# DAP-Link.net
KiCad netlist of a schematic drawn in Altium Designer
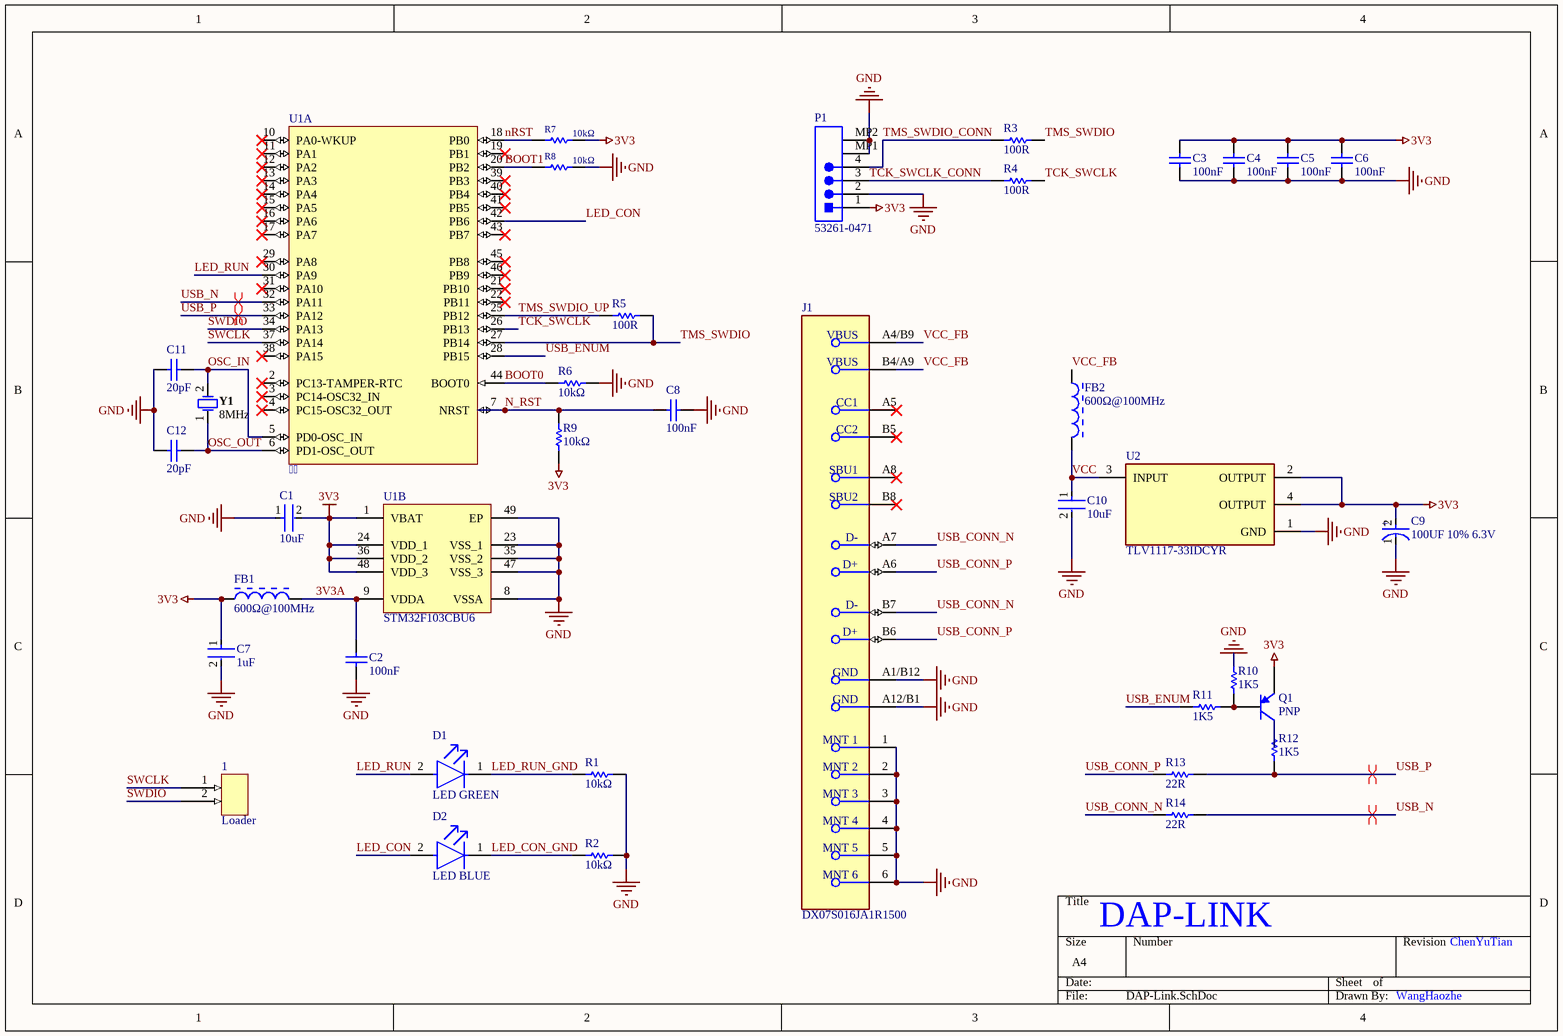
[diagram p0: DAP-Link.SchDoc]

(export (version "E")
  (design (tool "Eeschema 10.0.6"))
  (components
    (comp (ref "1") (value "Loader") (footprint "Loader") (libsource (lib "Loader") (part "Loader")))
    (comp (ref "C1")
      (value "10uF")
      (footprint "FP-CL10-IPC_C")
      (description "Cap Ceramic 10uF 25V X5R ±20% Pad SMD 0603 +85°C T/R")
      (fields (field (name "TOLERANCE") "20%"))
      (libsource (lib "Altium Content Vault") (part "b4654b650e69147ec39a6b967a45e02"))
    )
    (comp (ref "C2")
      (value "100nF")
      (footprint "CAPC1050X55X23ML05T13")
      (description "Chip Capacitor, 100 nF, +/- 10%, 16 V, -55 to 125 degC, 0402 (1005 Metric), RoHS, Tape and Reel")
      (fields (field (name "MANUFACTURER") "Samsung Electro-Mechanics"))
      (libsource (lib "Altium Content Vault") (part "CAP-NP-2"))
    )
    (comp (ref "C3")
      (value "100nF")
      (footprint "CAPC1050X55X23ML05T13")
      (description "Chip Capacitor, 100 nF, +/- 10%, 16 V, -55 to 125 degC, 0402 (1005 Metric), RoHS, Tape and Reel")
      (fields (field (name "MANUFACTURER") "Samsung Electro-Mechanics"))
      (libsource (lib "Altium Content Vault") (part "CAP-NP-2"))
    )
    (comp (ref "C4")
      (value "100nF")
      (footprint "CAPC1050X55X23ML05T13")
      (description "Chip Capacitor, 100 nF, +/- 10%, 16 V, -55 to 125 degC, 0402 (1005 Metric), RoHS, Tape and Reel")
      (fields (field (name "MANUFACTURER") "Samsung Electro-Mechanics"))
      (libsource (lib "Altium Content Vault") (part "CAP-NP-2"))
    )
    (comp (ref "C5")
      (value "100nF")
      (footprint "CAPC1050X55X23ML05T13")
      (description "Chip Capacitor, 100 nF, +/- 10%, 16 V, -55 to 125 degC, 0402 (1005 Metric), RoHS, Tape and Reel")
      (fields (field (name "MANUFACTURER") "Samsung Electro-Mechanics"))
      (libsource (lib "Altium Content Vault") (part "CAP-NP-2"))
    )
    (comp (ref "C6")
      (value "100nF")
      (footprint "CAPC1050X55X23ML05T13")
      (description "Chip Capacitor, 100 nF, +/- 10%, 16 V, -55 to 125 degC, 0402 (1005 Metric), RoHS, Tape and Reel")
      (fields (field (name "MANUFACTURER") "Samsung Electro-Mechanics"))
      (libsource (lib "Altium Content Vault") (part "CAP-NP-2"))
    )
    (comp (ref "C7")
      (value "1uF")
      (footprint "FP-CL542-IPC_C")
      (description "Cap Ceramic 1uF 25V X5R ±10% SMD 0402 +85°C Paper T/R")
      (fields (field (name "TOLERANCE") "10%"))
      (libsource (lib "Altium Content Vault") (part "b4654b650e69147ec39a6b967a45e02"))
    )
    (comp (ref "C8")
      (value "100nF")
      (footprint "CAPC1050X55X23ML05T13")
      (description "Chip Capacitor, 100 nF, +/- 10%, 16 V, -55 to 125 degC, 0402 (1005 Metric), RoHS, Tape and Reel")
      (fields (field (name "MANUFACTURER") "Samsung Electro-Mechanics"))
      (libsource (lib "Altium Content Vault") (part "CAP-NP-2"))
    )
    (comp (ref "C9")
      (value "100UF 10% 6.3V")
      (footprint "FP-TAJB-MFG")
      (description "100uF 6.3V  ±10% 1.7Ω 1210  SMD Tantalum Capacitor")
      (fields (field (name "TOLERANCE") "10%") (field (name "VOLTAGE") "6.3V"))
      (libsource (lib "Altium Content Vault") (part "203bc49f2ac43e59fd269a8c329ed05"))
    )
    (comp (ref "C10")
      (value "10uF")
      (footprint "FP-CL10-IPC_C")
      (description "Cap Ceramic 10uF 25V X5R ±20% Pad SMD 0603 +85°C T/R")
      (fields (field (name "TOLERANCE") "20%"))
      (libsource (lib "Altium Content Vault") (part "b4654b650e69147ec39a6b967a45e02"))
    )
    (comp (ref "C11")
      (value "20pF")
      (footprint "CAPC1608X90X30LL10T20")
      (description "Chip Capacitor, 20 pF, +/- 5%, 50 V, -55 to 85 degC, 0603 (1608 Metric), RoHS, Tape and Reel")
      (fields (field (name "MANUFACTURER") "Samsung Electro-Mechanics"))
      (libsource (lib "Altium Content Vault") (part "CAP-NP-2"))
    )
    (comp (ref "C12")
      (value "20pF")
      (footprint "CAPC1608X90X30LL10T20")
      (description "Chip Capacitor, 20 pF, +/- 5%, 50 V, -55 to 85 degC, 0603 (1608 Metric), RoHS, Tape and Reel")
      (fields (field (name "MANUFACTURER") "Samsung Electro-Mechanics"))
      (libsource (lib "Altium Content Vault") (part "CAP-NP-2"))
    )
    (comp (ref "D1")
      (value "LED GREEN")
      (footprint "FP-LTST-C190GKT-MFG")
      (description "LED GREEN CLEAR CHIP SMD")
      (fields (field (name "VOLTAGE") "2V"))
      (libsource (lib "Altium Content Vault") (part "8706943c75ba83719d021d2fdc84c58"))
    )
    (comp (ref "D2")
      (value "LED BLUE")
      (footprint "FP-LTST-C191TBKT-MFG")
      (description "LED BLUE CLEAR CHIP SMD")
      (libsource (lib "Altium Content Vault") (part "8706943c75ba83719d021d2fdc84c58"))
    )
    (comp (ref "FB1")
      (value "600Ω@100MHz")
      (footprint "MURA-BLM18-F-H1-CHIP-2_V")
      (fields (field (name "MANUFACTURER") "Murata") (field (name "PARTNUMBER") "BLM18AG601SN1D"))
      (libsource (lib "Altium Content Vault") (part "MURA-FB-2"))
    )
    (comp (ref "FB2")
      (value "600Ω@100MHz")
      (footprint "MURA-BLM18-F-H1-CHIP-2_V")
      (fields (field (name "MANUFACTURER") "Murata") (field (name "PARTNUMBER") "BLM18AG601SN1D"))
      (libsource (lib "Altium Content Vault") (part "MURA-FB-2"))
    )
    (comp (ref "J1")
      (value "DX07S016JA1R1500")
      (footprint "FP-DX07S016JA1R1500-MFG")
      (description "CONN RCP USB2.0 TYP C 24P SMD RA")
      (libsource (lib "Altium Content Vault") (part "7f3e9989102a0f22bff9cb010881d34"))
    )
    (comp (ref "P1")
      (value "53261-0471")
      (footprint "MOLEX-53261-0471_V")
      (description "Male Header, Pitch 1.25 mm, 1 x 4 Position, Height 3.4 mm, -40 to 85 degC, RoHS, Tape and Reel")
      (fields (field (name "MANUFACTURER") "Molex"))
      (libsource (lib "Altium Content Vault") (part "CN-1P-2M-R4_A"))
    )
    (comp (ref "Q1")
      (value "PNP")
      (footprint "INF-SOT23_N")
      (description "PNP Silicon Switching Transistor, 40 V VCEO, 200 mA IC, SOT23, Reel, Green")
      (fields (field (name "MANUFACTURER") "Infineon") (field (name "PARTNUMBER") "SMBT3906"))
      (libsource (lib "Altium Content Vault") (part "INF-BJTPNP-BEC-3"))
    )
    (comp (ref "R1")
      (value "10kΩ")
      (footprint "RESC1005X40X25NL05T05")
      (fields (field (name "MANUFACTURER") "Vishay Dale") (field (name "PART NUMBER") "CRCW040210K0FKED"))
      (libsource (lib "Altium Content Vault") (part "RES"))
    )
    (comp (ref "R2")
      (value "10kΩ")
      (footprint "RESC1005X40X25NL05T05")
      (fields (field (name "MANUFACTURER") "Vishay Dale") (field (name "PART NUMBER") "CRCW040210K0FKED"))
      (libsource (lib "Altium Content Vault") (part "RES"))
    )
    (comp (ref "R3")
      (value "100R")
      (footprint "RESC1608X55X25ML10T15")
      (description "Chip Resistor, 100 Ohm, +/- 1%, 0.1 W, -55 to 155 degC, 0603 (1608 Metric), RoHS, Tape and Reel")
      (fields (field (name "TOLERANCE") "1%") (field (name "MANUFACTURER") "Yageo"))
      (libsource (lib "Altium Content Vault") (part "RES-2"))
    )
    (comp (ref "R4")
      (value "100R")
      (footprint "RESC1608X55X25ML10T15")
      (description "Chip Resistor, 100 Ohm, +/- 1%, 0.1 W, -55 to 155 degC, 0603 (1608 Metric), RoHS, Tape and Reel")
      (fields (field (name "TOLERANCE") "1%") (field (name "MANUFACTURER") "Yageo"))
      (libsource (lib "Altium Content Vault") (part "RES-2"))
    )
    (comp (ref "R5")
      (value "100R")
      (footprint "RESC1608X55X25ML10T15")
      (description "Chip Resistor, 100 Ohm, +/- 1%, 0.1 W, -55 to 155 degC, 0603 (1608 Metric), RoHS, Tape and Reel")
      (fields (field (name "TOLERANCE") "1%") (field (name "MANUFACTURER") "Yageo"))
      (libsource (lib "Altium Content Vault") (part "RES-2"))
    )
    (comp (ref "R6")
      (value "10kΩ")
      (footprint "RESC1005X40X25NL05T05")
      (fields (field (name "MANUFACTURER") "Vishay Dale") (field (name "PART NUMBER") "CRCW040210K0FKED"))
      (libsource (lib "Altium Content Vault") (part "RES"))
    )
    (comp (ref "R7")
      (value "10kΩ")
      (footprint "RESC1005X40X25NL05T05")
      (fields (field (name "MANUFACTURER") "Vishay Dale") (field (name "PART NUMBER") "CRCW040210K0FKED"))
      (libsource (lib "Altium Content Vault") (part "RES"))
    )
    (comp (ref "R8")
      (value "10kΩ")
      (footprint "RESC1005X40X25NL05T05")
      (fields (field (name "MANUFACTURER") "Vishay Dale") (field (name "PART NUMBER") "CRCW040210K0FKED"))
      (libsource (lib "Altium Content Vault") (part "RES"))
    )
    (comp (ref "R9")
      (value "10kΩ")
      (footprint "RESC1005X40X25NL05T05")
      (fields (field (name "MANUFACTURER") "Vishay Dale") (field (name "PART NUMBER") "CRCW040210K0FKED"))
      (libsource (lib "Altium Content Vault") (part "RES"))
    )
    (comp (ref "R10")
      (value "1K5")
      (footprint "RESC1005X40X25ML05T10")
      (fields (field (name "MANUFACTURER") "Yageo / Phycomp") (field (name "PART NUMBER") "RC0402FR-071K5L"))
      (libsource (lib "Altium Content Vault") (part "RES"))
    )
    (comp (ref "R11")
      (value "1K5")
      (footprint "RESC1005X40X25ML05T10")
      (fields (field (name "MANUFACTURER") "Yageo / Phycomp") (field (name "PART NUMBER") "RC0402FR-071K5L"))
      (libsource (lib "Altium Content Vault") (part "RES"))
    )
    (comp (ref "R12")
      (value "1K5")
      (footprint "RESC1005X40X25ML05T10")
      (fields (field (name "MANUFACTURER") "Yageo / Phycomp") (field (name "PART NUMBER") "RC0402FR-071K5L"))
      (libsource (lib "Altium Content Vault") (part "RES"))
    )
    (comp (ref "R13")
      (value "22R")
      (footprint "RESC1005X40X25LL05T10")
      (fields (field (name "MANUFACTURER") "Yageo / Phycomp") (field (name "PART NUMBER") "RC0402FR-0722RL"))
      (libsource (lib "Altium Content Vault") (part "RES"))
    )
    (comp (ref "R14")
      (value "22R")
      (footprint "RESC1005X40X25LL05T10")
      (fields (field (name "MANUFACTURER") "Yageo / Phycomp") (field (name "PART NUMBER") "RC0402FR-0722RL"))
      (libsource (lib "Altium Content Vault") (part "RES"))
    )
    (comp (ref "U1")
      (value "")
      (footprint "STM-UFQFPN48_N")
      (fields (field (name "PARTNUMBER") "STM32F103CBU6"))
      (libsource (lib "Altium Content Vault") (part "MC-ARM-STM32F103X8_B-SQ49"))
    )
    (comp (ref "U2")
      (value "TLV1117-33IDCYR")
      (footprint "FP-DCY0004A-MFG")
      (description "IC REG LIN 3.3V 800MA SOT223-4")
      (fields
        (field (name "MANUFACTURER") "Texas Instruments")
        (field (name "OCTOPART") "https://octopart.com/tlv1117-33idcyr-texas+instruments-669250")
      )
      (libsource (lib "Altium Content Vault") (part "d420fb9686013fb832e66295cdf4acf"))
    )
    (comp (ref "Y1")
      (value "8MHz")
      (footprint "NDK-NX3225GD-8MHZ-STD-CRA-3_V")
      (description "Crystal Unit, 8 MHz, 8 pF, -40 to 150 degC, 2-Pin SMD, RoHS, Tape and Reel")
      (fields (field (name "MANUFACTURER") "NDK"))
      (libsource (lib "Altium Content Vault") (part "XTAL-1-2-2"))
    )
  )
  (nets
    (net (code "1") (name "/3V3A") (class "Default")
      (node (ref "C2") (pin "2") (pinfunction "2_2") (pintype "passive"))
      (node (ref "FB1") (pin "2") (pinfunction "2_2") (pintype "passive"))
      (node (ref "U1") (pin "9") (pinfunction "VDDA_9") (pintype "power_in"))
    )
    (net (code "2") (name "/BOOT0") (class "Default")
      (node (ref "R6") (pin "1") (pinfunction "1_1") (pintype "passive"))
      (node (ref "U1") (pin "44") (pinfunction "BOOT0_44") (pintype "input"))
    )
    (net (code "3") (name "/BOOT1") (class "Default")
      (node (ref "R8") (pin "1") (pinfunction "1_1") (pintype "passive"))
      (node (ref "U1") (pin "20") (pinfunction "PB2_20") (pintype "bidirectional"))
    )
    (net (code "4") (name "/LED_CON") (class "Default")
      (node (ref "D2") (pin "2") (pinfunction "A_2") (pintype "passive"))
      (node (ref "U1") (pin "42") (pinfunction "PB6_42") (pintype "bidirectional"))
    )
    (net (code "5") (name "/LED_CON_GND") (class "Default")
      (node (ref "D2") (pin "1") (pinfunction "C_1") (pintype "passive"))
      (node (ref "R2") (pin "1") (pinfunction "1_1") (pintype "passive"))
    )
    (net (code "6") (name "/LED_RUN") (class "Default")
      (node (ref "D1") (pin "2") (pinfunction "A_2") (pintype "passive"))
      (node (ref "U1") (pin "30") (pinfunction "PA9_30") (pintype "bidirectional"))
    )
    (net (code "7") (name "/LED_RUN_GND") (class "Default")
      (node (ref "D1") (pin "1") (pinfunction "C_1") (pintype "passive"))
      (node (ref "R1") (pin "1") (pinfunction "1_1") (pintype "passive"))
    )
    (net (code "8") (name "/N_RST") (class "Default")
      (node (ref "C8") (pin "1") (pinfunction "1_1") (pintype "passive"))
      (node (ref "R9") (pin "1") (pinfunction "1_1") (pintype "passive"))
      (node (ref "U1") (pin "7") (pinfunction "NRST_7") (pintype "bidirectional"))
    )
    (net (code "9") (name "/OSC_IN") (class "Default")
      (node (ref "C11") (pin "2") (pinfunction "2_2") (pintype "passive"))
      (node (ref "U1") (pin "5") (pinfunction "PD0-OSC_IN_5") (pintype "bidirectional"))
      (node (ref "Y1") (pin "2") (pinfunction "2_2") (pintype "passive"))
    )
    (net (code "10") (name "/OSC_OUT") (class "Default")
      (node (ref "C12") (pin "2") (pinfunction "2_2") (pintype "passive"))
      (node (ref "U1") (pin "6") (pinfunction "PD1-OSC_OUT_6") (pintype "bidirectional"))
      (node (ref "Y1") (pin "1") (pinfunction "1_1") (pintype "passive"))
    )
    (net (code "11") (name "/SWCLK") (class "Default")
      (node (ref "1") (pin "1") (pintype "input"))
      (node (ref "U1") (pin "37") (pinfunction "PA14_37") (pintype "bidirectional"))
    )
    (net (code "12") (name "/SWDIO") (class "Default")
      (node (ref "1") (pin "2") (pintype "input"))
      (node (ref "U1") (pin "34") (pinfunction "PA13_34") (pintype "bidirectional"))
    )
    (net (code "13") (name "/TCK_SWCLK") (class "Default")
      (node (ref "R4") (pin "2") (pinfunction "2_2") (pintype "passive"))
      (node (ref "U1") (pin "26") (pinfunction "PB13_26") (pintype "bidirectional"))
    )
    (net (code "14") (name "/TCK_SWCLK_CONN") (class "Default")
      (node (ref "P1") (pin "3") (pinfunction "3_3") (pintype "passive"))
      (node (ref "R4") (pin "1") (pinfunction "1_1") (pintype "passive"))
    )
    (net (code "15") (name "/TMS_SWDIO") (class "Default")
      (node (ref "R3") (pin "2") (pinfunction "2_2") (pintype "passive"))
      (node (ref "R5") (pin "2") (pinfunction "2_2") (pintype "passive"))
      (node (ref "U1") (pin "27") (pinfunction "PB14_27") (pintype "bidirectional"))
    )
    (net (code "16") (name "/TMS_SWDIO_CONN") (class "Default")
      (node (ref "P1") (pin "4") (pinfunction "4_4") (pintype "passive"))
      (node (ref "R3") (pin "1") (pinfunction "1_1") (pintype "passive"))
    )
    (net (code "17") (name "/TMS_SWDIO_UP") (class "Default")
      (node (ref "R5") (pin "1") (pinfunction "1_1") (pintype "passive"))
      (node (ref "U1") (pin "25") (pinfunction "PB12_25") (pintype "bidirectional"))
    )
    (net (code "18") (name "/USB_CONN_N") (class "Default")
      (node (ref "J1") (pin "A7") (pinfunction "D-_A7") (pintype "bidirectional"))
      (node (ref "J1") (pin "B7") (pinfunction "D-_B7") (pintype "bidirectional"))
      (node (ref "R14") (pin "1") (pinfunction "1_1") (pintype "passive"))
    )
    (net (code "19") (name "/USB_CONN_P") (class "Default")
      (node (ref "J1") (pin "A6") (pinfunction "D+_A6") (pintype "bidirectional"))
      (node (ref "J1") (pin "B6") (pinfunction "D+_B6") (pintype "bidirectional"))
      (node (ref "R13") (pin "1") (pinfunction "1_1") (pintype "passive"))
    )
    (net (code "20") (name "/USB_ENUM") (class "Default")
      (node (ref "R11") (pin "2") (pinfunction "2_2") (pintype "passive"))
      (node (ref "U1") (pin "28") (pinfunction "PB15_28") (pintype "bidirectional"))
    )
    (net (code "21") (name "/USB_N") (class "Default")
      (node (ref "R14") (pin "2") (pinfunction "2_2") (pintype "passive"))
      (node (ref "U1") (pin "32") (pinfunction "PA11_32") (pintype "bidirectional"))
    )
    (net (code "22") (name "/USB_P") (class "Default")
      (node (ref "R12") (pin "1") (pinfunction "1_1") (pintype "passive"))
      (node (ref "R13") (pin "2") (pinfunction "2_2") (pintype "passive"))
      (node (ref "U1") (pin "33") (pinfunction "PA12_33") (pintype "bidirectional"))
    )
    (net (code "23") (name "/VCC") (class "Default")
      (node (ref "C10") (pin "1") (pinfunction "1_1") (pintype "passive"))
      (node (ref "FB2") (pin "2") (pinfunction "2_2") (pintype "passive"))
      (node (ref "U2") (pin "3") (pinfunction "INPUT_3") (pintype "power_in"))
    )
    (net (code "24") (name "/VCC_FB") (class "Default")
      (node (ref "FB2") (pin "1") (pinfunction "1_1") (pintype "passive"))
      (node (ref "J1") (pin "A4/B9") (pinfunction "VBUS_A4/B9") (pintype "power_in"))
      (node (ref "J1") (pin "B4/A9") (pinfunction "VBUS_B4/A9") (pintype "power_in"))
    )
    (net (code "25") (name "/nRST") (class "Default")
      (node (ref "R7") (pin "1") (pinfunction "1_1") (pintype "passive"))
      (node (ref "U1") (pin "18") (pinfunction "PB0_18") (pintype "bidirectional"))
    )
    (net (code "26") (name "3V3") (class "Default")
      (node (ref "C1") (pin "2") (pinfunction "2_2") (pintype "passive"))
      (node (ref "C3") (pin "2") (pinfunction "2_2") (pintype "passive"))
      (node (ref "C4") (pin "2") (pinfunction "2_2") (pintype "passive"))
      (node (ref "C5") (pin "2") (pinfunction "2_2") (pintype "passive"))
      (node (ref "C6") (pin "2") (pinfunction "2_2") (pintype "passive"))
      (node (ref "C7") (pin "1") (pinfunction "1_1") (pintype "passive"))
      (node (ref "C9") (pin "2") (pinfunction "A_2") (pintype "passive"))
      (node (ref "FB1") (pin "1") (pinfunction "1_1") (pintype "passive"))
      (node (ref "P1") (pin "1") (pinfunction "1_1") (pintype "passive"))
      (node (ref "Q1") (pin "2") (pinfunction "E_2") (pintype "passive"))
      (node (ref "R7") (pin "2") (pinfunction "2_2") (pintype "passive"))
      (node (ref "R9") (pin "2") (pinfunction "2_2") (pintype "passive"))
      (node (ref "U1") (pin "1") (pinfunction "VBAT_1") (pintype "power_in"))
      (node (ref "U1") (pin "24") (pinfunction "VDD_1_24") (pintype "power_in"))
      (node (ref "U1") (pin "36") (pinfunction "VDD_2_36") (pintype "power_in"))
      (node (ref "U1") (pin "48") (pinfunction "VDD_3_48") (pintype "power_in"))
      (node (ref "U2") (pin "2") (pinfunction "OUTPUT_2") (pintype "power_in"))
      (node (ref "U2") (pin "4") (pinfunction "OUTPUT_4") (pintype "power_in"))
    )
    (net (code "27") (name "GND") (class "Default")
      (node (ref "C1") (pin "1") (pinfunction "1_1") (pintype "passive"))
      (node (ref "C10") (pin "2") (pinfunction "2_2") (pintype "passive"))
      (node (ref "C11") (pin "1") (pinfunction "1_1") (pintype "passive"))
      (node (ref "C12") (pin "1") (pinfunction "1_1") (pintype "passive"))
      (node (ref "C2") (pin "1") (pinfunction "1_1") (pintype "passive"))
      (node (ref "C3") (pin "1") (pinfunction "1_1") (pintype "passive"))
      (node (ref "C4") (pin "1") (pinfunction "1_1") (pintype "passive"))
      (node (ref "C5") (pin "1") (pinfunction "1_1") (pintype "passive"))
      (node (ref "C6") (pin "1") (pinfunction "1_1") (pintype "passive"))
      (node (ref "C7") (pin "2") (pinfunction "2_2") (pintype "passive"))
      (node (ref "C8") (pin "2") (pinfunction "2_2") (pintype "passive"))
      (node (ref "C9") (pin "1") (pinfunction "C_1") (pintype "passive"))
      (node (ref "J1") (pin "1") (pinfunction "MNT_1_1") (pintype "passive"))
      (node (ref "J1") (pin "2") (pinfunction "MNT_2_2") (pintype "passive"))
      (node (ref "J1") (pin "3") (pinfunction "MNT_3_3") (pintype "passive"))
      (node (ref "J1") (pin "4") (pinfunction "MNT_4_4") (pintype "passive"))
      (node (ref "J1") (pin "5") (pinfunction "MNT_5_5") (pintype "passive"))
      (node (ref "J1") (pin "6") (pinfunction "MNT_6_6") (pintype "passive"))
      (node (ref "J1") (pin "A1/B12") (pinfunction "GND_A1/B12") (pintype "power_in"))
      (node (ref "J1") (pin "A12/B1") (pinfunction "GND_A12/B1") (pintype "power_in"))
      (node (ref "P1") (pin "2") (pinfunction "2_2") (pintype "passive"))
      (node (ref "P1") (pin "MP1") (pinfunction "MP1_MP1") (pintype "passive"))
      (node (ref "P1") (pin "MP2") (pinfunction "MP2_MP2") (pintype "passive"))
      (node (ref "R1") (pin "2") (pinfunction "2_2") (pintype "passive"))
      (node (ref "R10") (pin "1") (pinfunction "1_1") (pintype "passive"))
      (node (ref "R2") (pin "2") (pinfunction "2_2") (pintype "passive"))
      (node (ref "R6") (pin "2") (pinfunction "2_2") (pintype "passive"))
      (node (ref "R8") (pin "2") (pinfunction "2_2") (pintype "passive"))
      (node (ref "U1") (pin "23") (pinfunction "VSS_1_23") (pintype "power_in"))
      (node (ref "U1") (pin "35") (pinfunction "VSS_2_35") (pintype "power_in"))
      (node (ref "U1") (pin "47") (pinfunction "VSS_3_47") (pintype "power_in"))
      (node (ref "U1") (pin "49") (pinfunction "EP_49") (pintype "power_in"))
      (node (ref "U1") (pin "8") (pinfunction "VSSA_8") (pintype "power_in"))
      (node (ref "U2") (pin "1") (pinfunction "GND_1") (pintype "power_in"))
    )
    (net (code "28") (name "Net-(Q1-B)") (class "Default")
      (node (ref "Q1") (pin "1") (pinfunction "B_1") (pintype "passive"))
      (node (ref "R10") (pin "2") (pinfunction "2_2") (pintype "passive"))
      (node (ref "R11") (pin "1") (pinfunction "1_1") (pintype "passive"))
    )
    (net (code "29") (name "Net-(Q1-C)") (class "Default")
      (node (ref "Q1") (pin "3") (pinfunction "C_3") (pintype "passive"))
      (node (ref "R12") (pin "2") (pinfunction "2_2") (pintype "passive"))
    )
    (net (code "30") (name "unconnected-(J1-CC1-PadA5)") (class "Default")
      (node (ref "J1") (pin "A5") (pinfunction "CC1_A5") (pintype "passive+no_connect"))
    )
    (net (code "31") (name "unconnected-(J1-CC2-PadB5)") (class "Default")
      (node (ref "J1") (pin "B5") (pinfunction "CC2_B5") (pintype "passive+no_connect"))
    )
    (net (code "32") (name "unconnected-(J1-SBU1-PadA8)") (class "Default")
      (node (ref "J1") (pin "A8") (pinfunction "SBU1_A8") (pintype "passive+no_connect"))
    )
    (net (code "33") (name "unconnected-(J1-SBU2-PadB8)") (class "Default")
      (node (ref "J1") (pin "B8") (pinfunction "SBU2_B8") (pintype "passive+no_connect"))
    )
    (net (code "34") (name "unconnected-(U1A-PA0-WKUP-Pad10)") (class "Default")
      (node (ref "U1") (pin "10") (pinfunction "PA0-WKUP_10") (pintype "bidirectional+no_connect"))
    )
    (net (code "35") (name "unconnected-(U1A-PA1-Pad11)") (class "Default")
      (node (ref "U1") (pin "11") (pinfunction "PA1_11") (pintype "bidirectional+no_connect"))
    )
    (net (code "36") (name "unconnected-(U1A-PA2-Pad12)") (class "Default")
      (node (ref "U1") (pin "12") (pinfunction "PA2_12") (pintype "bidirectional+no_connect"))
    )
    (net (code "37") (name "unconnected-(U1A-PA3-Pad13)") (class "Default")
      (node (ref "U1") (pin "13") (pinfunction "PA3_13") (pintype "bidirectional+no_connect"))
    )
    (net (code "38") (name "unconnected-(U1A-PA4-Pad14)") (class "Default")
      (node (ref "U1") (pin "14") (pinfunction "PA4_14") (pintype "bidirectional+no_connect"))
    )
    (net (code "39") (name "unconnected-(U1A-PA5-Pad15)") (class "Default")
      (node (ref "U1") (pin "15") (pinfunction "PA5_15") (pintype "bidirectional+no_connect"))
    )
    (net (code "40") (name "unconnected-(U1A-PA6-Pad16)") (class "Default")
      (node (ref "U1") (pin "16") (pinfunction "PA6_16") (pintype "bidirectional+no_connect"))
    )
    (net (code "41") (name "unconnected-(U1A-PA7-Pad17)") (class "Default")
      (node (ref "U1") (pin "17") (pinfunction "PA7_17") (pintype "bidirectional+no_connect"))
    )
    (net (code "42") (name "unconnected-(U1A-PA8-Pad29)") (class "Default")
      (node (ref "U1") (pin "29") (pinfunction "PA8_29") (pintype "bidirectional+no_connect"))
    )
    (net (code "43") (name "unconnected-(U1A-PA10-Pad31)") (class "Default")
      (node (ref "U1") (pin "31") (pinfunction "PA10_31") (pintype "bidirectional+no_connect"))
    )
    (net (code "44") (name "unconnected-(U1A-PA15-Pad38)") (class "Default")
      (node (ref "U1") (pin "38") (pinfunction "PA15_38") (pintype "bidirectional+no_connect"))
    )
    (net (code "45") (name "unconnected-(U1A-PB1-Pad19)") (class "Default")
      (node (ref "U1") (pin "19") (pinfunction "PB1_19") (pintype "bidirectional+no_connect"))
    )
    (net (code "46") (name "unconnected-(U1A-PB3-Pad39)") (class "Default")
      (node (ref "U1") (pin "39") (pinfunction "PB3_39") (pintype "bidirectional+no_connect"))
    )
    (net (code "47") (name "unconnected-(U1A-PB4-Pad40)") (class "Default")
      (node (ref "U1") (pin "40") (pinfunction "PB4_40") (pintype "bidirectional+no_connect"))
    )
    (net (code "48") (name "unconnected-(U1A-PB5-Pad41)") (class "Default")
      (node (ref "U1") (pin "41") (pinfunction "PB5_41") (pintype "bidirectional+no_connect"))
    )
    (net (code "49") (name "unconnected-(U1A-PB7-Pad43)") (class "Default")
      (node (ref "U1") (pin "43") (pinfunction "PB7_43") (pintype "bidirectional+no_connect"))
    )
    (net (code "50") (name "unconnected-(U1A-PB8-Pad45)") (class "Default")
      (node (ref "U1") (pin "45") (pinfunction "PB8_45") (pintype "bidirectional+no_connect"))
    )
    (net (code "51") (name "unconnected-(U1A-PB9-Pad46)") (class "Default")
      (node (ref "U1") (pin "46") (pinfunction "PB9_46") (pintype "bidirectional+no_connect"))
    )
    (net (code "52") (name "unconnected-(U1A-PB10-Pad21)") (class "Default")
      (node (ref "U1") (pin "21") (pinfunction "PB10_21") (pintype "bidirectional+no_connect"))
    )
    (net (code "53") (name "unconnected-(U1A-PB11-Pad22)") (class "Default")
      (node (ref "U1") (pin "22") (pinfunction "PB11_22") (pintype "bidirectional+no_connect"))
    )
    (net (code "54") (name "unconnected-(U1A-PC13-TAMPER-RTC-Pad2)") (class "Default")
      (node (ref "U1") (pin "2") (pinfunction "PC13-TAMPER-RTC_2") (pintype "bidirectional+no_connect"))
    )
    (net (code "55") (name "unconnected-(U1A-PC14-OSC32_IN-Pad3)") (class "Default")
      (node (ref "U1") (pin "3") (pinfunction "PC14-OSC32_IN_3") (pintype "bidirectional+no_connect"))
    )
    (net (code "56") (name "unconnected-(U1A-PC15-OSC32_OUT-Pad4)") (class "Default")
      (node (ref "U1") (pin "4") (pinfunction "PC15-OSC32_OUT_4") (pintype "bidirectional+no_connect"))
    )
  )
)
